# untitled.net
KiCad netlist of a schematic drawn in EAGLE
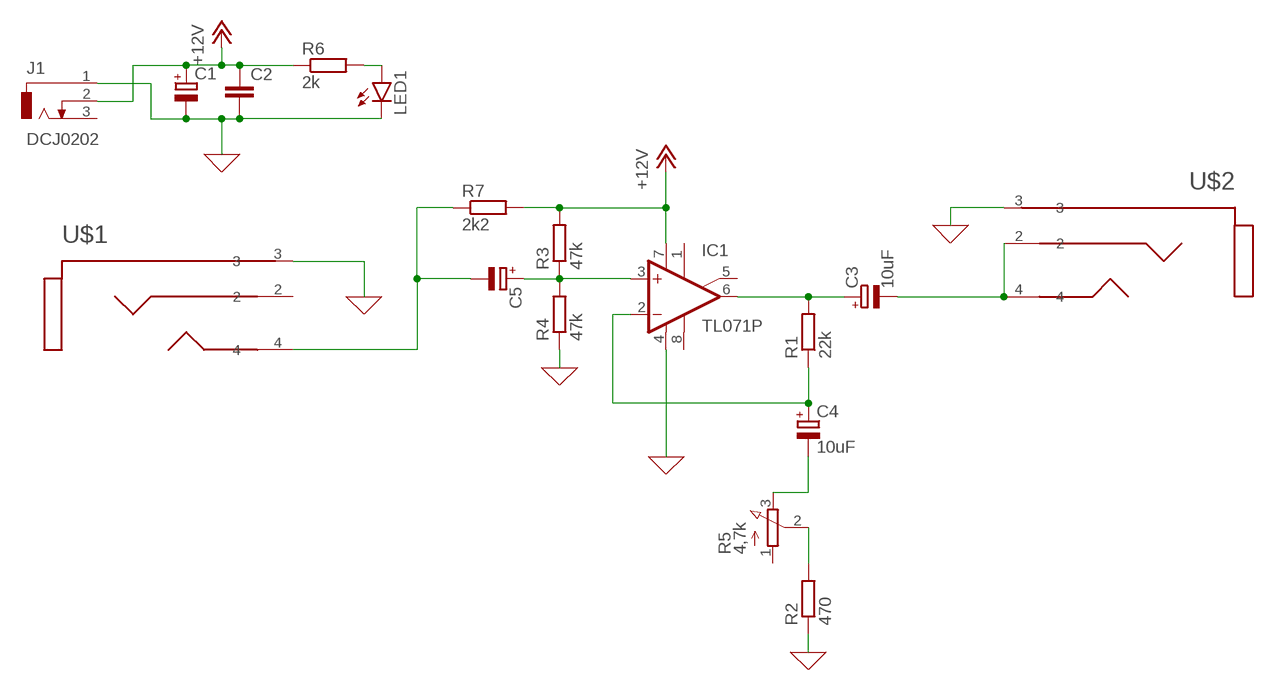
[diagram p0: schematic, sheet 1]

(export (version "E")
  (design (tool "Eeschema 10.0.6"))
  (components
    (comp (ref "C1")
      (value "CPOL-EUE2,5-6E")
      (footprint "eagle-import:E2,5-6E")
      (libsource (lib "eagle-import") (part "CPOL-EUE2,5-6E"))
    )
    (comp (ref "C2")
      (value "C-EU025-025X050")
      (footprint "eagle-import:C025-025X050")
      (libsource (lib "eagle-import") (part "C-EU025-025X050"))
    )
    (comp (ref "C3")
      (value "10uF")
      (footprint "eagle-import:E2,5-6E")
      (libsource (lib "eagle-import") (part "CPOL-EUE2,5-6E"))
    )
    (comp (ref "C4")
      (value "10uF")
      (footprint "eagle-import:E2,5-6E")
      (libsource (lib "eagle-import") (part "CPOL-EUE2,5-6E"))
    )
    (comp (ref "C5")
      (value "CPOL-EUE2,5-6E")
      (footprint "eagle-import:E2,5-6E")
      (libsource (lib "eagle-import") (part "CPOL-EUE2,5-6E"))
    )
    (comp (ref "IC1")
      (value "TL071P")
      (footprint "eagle-import:DIL08")
      (libsource (lib "eagle-import") (part "TL071P"))
    )
    (comp (ref "J1")
      (value "DCJ0202")
      (footprint "eagle-import:DCJ0202")
      (libsource (lib "eagle-import") (part "DCJ0202"))
    )
    (comp (ref "LED1")
      (value "LED5MM")
      (footprint "eagle-import:LED5MM")
      (libsource (lib "eagle-import") (part "LED5MM"))
    )
    (comp (ref "R1")
      (value "22k")
      (footprint "eagle-import:0207_10")
      (libsource (lib "eagle-import") (part "R-EU_0207/10"))
    )
    (comp (ref "R2")
      (value "470")
      (footprint "eagle-import:0207_10")
      (libsource (lib "eagle-import") (part "R-EU_0207/10"))
    )
    (comp (ref "R3")
      (value "47k")
      (footprint "eagle-import:0207_10")
      (libsource (lib "eagle-import") (part "R-EU_0207/10"))
    )
    (comp (ref "R4")
      (value "47k")
      (footprint "eagle-import:0207_10")
      (libsource (lib "eagle-import") (part "R-EU_0207/10"))
    )
    (comp (ref "R5")
      (value "4,7k")
      (footprint "eagle-import:3RP_1610N")
      (libsource (lib "eagle-import") (part "3RP/1610N"))
    )
    (comp (ref "R6")
      (value "2k")
      (footprint "eagle-import:0207_10")
      (libsource (lib "eagle-import") (part "R-EU_0207/10"))
    )
    (comp (ref "R7")
      (value "2k2")
      (footprint "eagle-import:0207_10")
      (libsource (lib "eagle-import") (part "R-EU_0207/10"))
    )
    (comp (ref "U$1")
      (value "PJ321")
      (footprint "eagle-import:PJ321")
      (libsource (lib "eagle-import") (part "PJ321"))
    )
    (comp (ref "U$2")
      (value "PJ321")
      (footprint "eagle-import:PJ321")
      (libsource (lib "eagle-import") (part "PJ321"))
    )
  )
  (nets
    (net (code "1") (name "+12V") (class "Default")
      (node (ref "C1") (pin "+") (pinfunction "+_+") (pintype "passive"))
      (node (ref "C2") (pin "1") (pinfunction "1_1") (pintype "passive"))
      (node (ref "IC1") (pin "7") (pinfunction "V+_7") (pintype "power_in"))
      (node (ref "J1") (pin "2") (pinfunction "2_2") (pintype "passive"))
      (node (ref "R3") (pin "2") (pinfunction "2_2") (pintype "passive"))
      (node (ref "R6") (pin "1") (pinfunction "1_1") (pintype "passive"))
      (node (ref "R7") (pin "2") (pinfunction "2_2") (pintype "passive"))
    )
    (net (code "2") (name "GND") (class "Default")
      (node (ref "C1") (pin "-") (pinfunction "-_-") (pintype "passive"))
      (node (ref "C2") (pin "2") (pinfunction "2_2") (pintype "passive"))
      (node (ref "IC1") (pin "4") (pinfunction "V-_4") (pintype "power_in"))
      (node (ref "J1") (pin "1") (pinfunction "1_1") (pintype "passive"))
      (node (ref "LED1") (pin "K") (pinfunction "C_K") (pintype "passive"))
      (node (ref "R2") (pin "1") (pinfunction "1_1") (pintype "passive"))
      (node (ref "R4") (pin "1") (pinfunction "1_1") (pintype "passive"))
      (node (ref "U$1") (pin "3") (pinfunction "3_3") (pintype "bidirectional"))
      (node (ref "U$2") (pin "3") (pinfunction "3_3") (pintype "bidirectional"))
    )
    (net (code "3") (name "Net-(C3-Pad-)") (class "Default")
      (node (ref "C3") (pin "-") (pinfunction "-_-") (pintype "passive"))
      (node (ref "U$2") (pin "2") (pinfunction "2_2") (pintype "bidirectional"))
      (node (ref "U$2") (pin "4") (pinfunction "4_4") (pintype "bidirectional"))
    )
    (net (code "4") (name "Net-(C5-Pad-)") (class "Default")
      (node (ref "C5") (pin "-") (pinfunction "-_-") (pintype "passive"))
      (node (ref "R7") (pin "1") (pinfunction "1_1") (pintype "passive"))
      (node (ref "U$1") (pin "4") (pinfunction "4_4") (pintype "bidirectional"))
    )
    (net (code "5") (name "Net-(IC1-+IN)") (class "Default")
      (node (ref "C5") (pin "+") (pinfunction "+_+") (pintype "passive"))
      (node (ref "IC1") (pin "3") (pinfunction "+IN_3") (pintype "input"))
      (node (ref "R3") (pin "1") (pinfunction "1_1") (pintype "passive"))
      (node (ref "R4") (pin "2") (pinfunction "2_2") (pintype "passive"))
    )
    (net (code "6") (name "Net-(IC1--IN)") (class "Default")
      (node (ref "C4") (pin "+") (pinfunction "+_+") (pintype "passive"))
      (node (ref "IC1") (pin "2") (pinfunction "-IN_2") (pintype "input"))
      (node (ref "R1") (pin "1") (pinfunction "1_1") (pintype "passive"))
    )
    (net (code "7") (name "Net-(IC1-OUT)") (class "Default")
      (node (ref "C3") (pin "+") (pinfunction "+_+") (pintype "passive"))
      (node (ref "IC1") (pin "6") (pinfunction "OUT_6") (pintype "output"))
      (node (ref "R1") (pin "2") (pinfunction "2_2") (pintype "passive"))
    )
    (net (code "8") (name "Net-(LED1-PadA)") (class "Default")
      (node (ref "LED1") (pin "A") (pinfunction "A_A") (pintype "passive"))
      (node (ref "R6") (pin "2") (pinfunction "2_2") (pintype "passive"))
    )
    (net (code "9") (name "Net-(R5-E)") (class "Default")
      (node (ref "C4") (pin "-") (pinfunction "-_-") (pintype "passive"))
      (node (ref "R5") (pin "3") (pinfunction "E_3") (pintype "passive"))
    )
    (net (code "10") (name "Net-(R5-S)") (class "Default")
      (node (ref "R2") (pin "2") (pinfunction "2_2") (pintype "passive"))
      (node (ref "R5") (pin "2") (pinfunction "S_2") (pintype "passive"))
    )
    (net (code "11") (name "unconnected-(IC1-ON1-Pad1)") (class "Default")
      (node (ref "IC1") (pin "1") (pinfunction "ON1_1") (pintype "passive"))
    )
    (net (code "12") (name "unconnected-(IC1-ON2-Pad5)") (class "Default")
      (node (ref "IC1") (pin "5") (pinfunction "ON2_5") (pintype "passive"))
    )
    (net (code "13") (name "unconnected-(IC1-OPT-Pad8)") (class "Default")
      (node (ref "IC1") (pin "8") (pinfunction "OPT_8") (pintype "passive"))
    )
    (net (code "14") (name "unconnected-(J1-Pad3)") (class "Default")
      (node (ref "J1") (pin "3") (pinfunction "3_3") (pintype "passive"))
    )
    (net (code "15") (name "unconnected-(R5-A-Pad1)") (class "Default")
      (node (ref "R5") (pin "1") (pinfunction "A_1") (pintype "passive"))
    )
    (net (code "16") (name "unconnected-(U$1-Pad2)") (class "Default")
      (node (ref "U$1") (pin "2") (pinfunction "2_2") (pintype "bidirectional"))
    )
  )
)
